# GPRS.net
KiCad netlist of a schematic drawn in Altium Designer
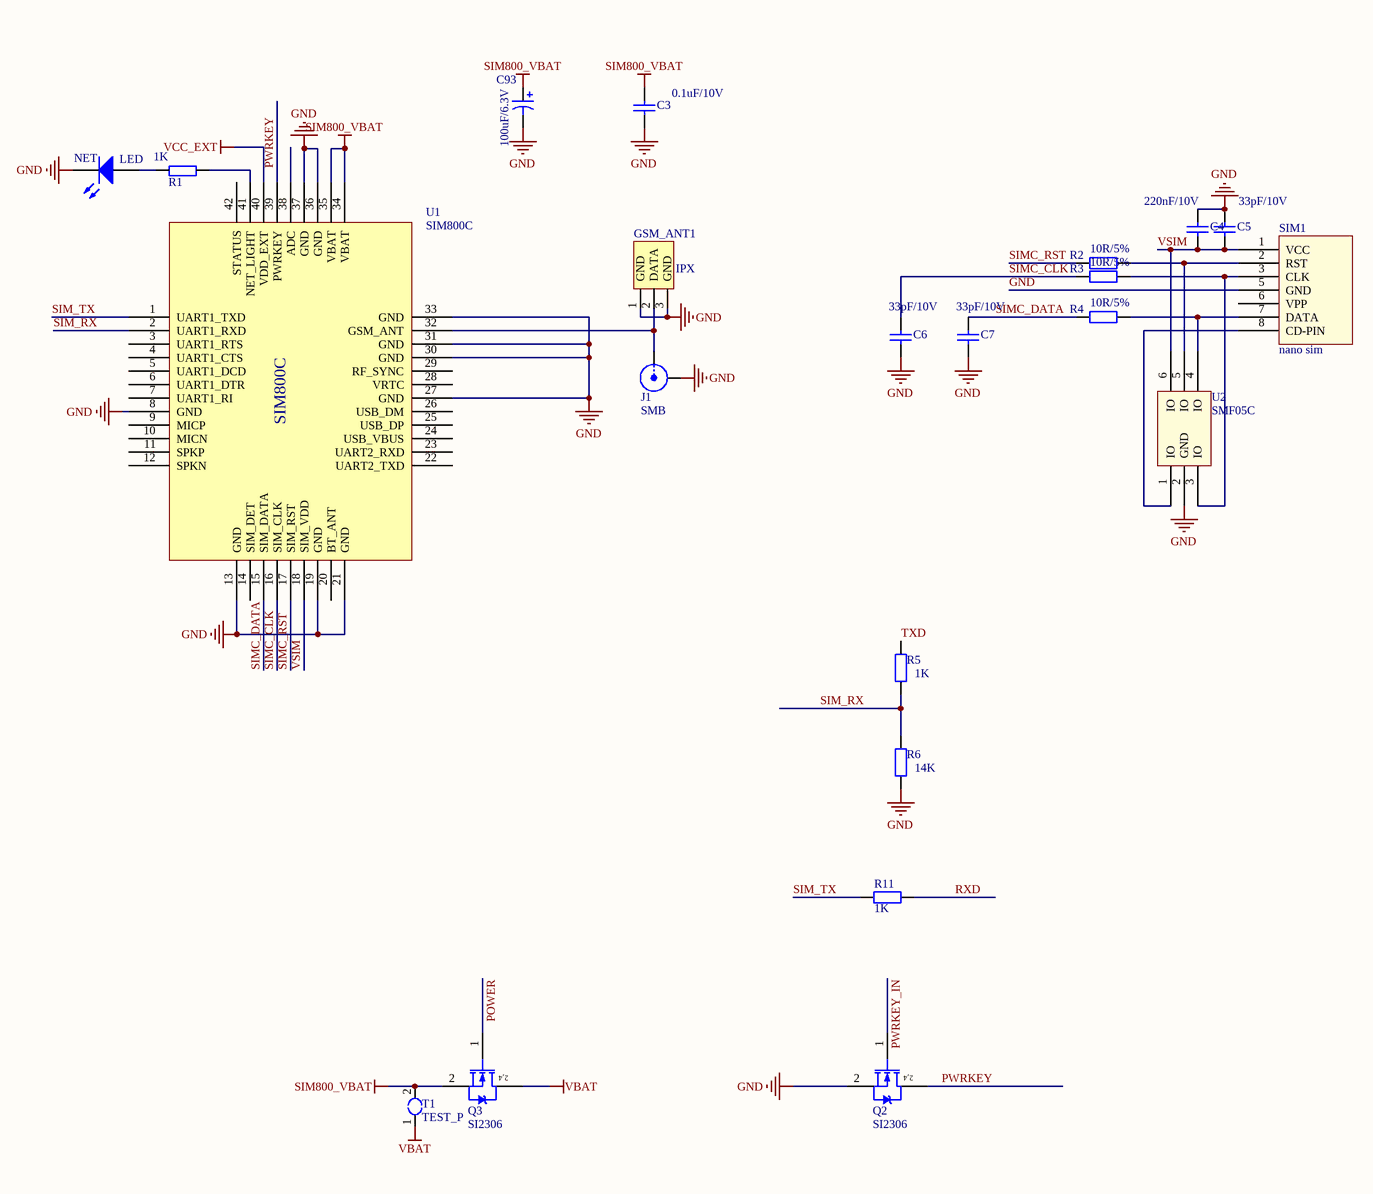
[diagram p0: GPRS.SchDoc]

(export (version "E")
  (design (tool "Eeschema 10.0.6"))
  (components
    (comp (ref "C3")
      (value "0.1uF/10V")
      (footprint "0603C")
      (description "Capacitor")
      (fields (field (name "PUBLISHER") "Altium Limited"))
      (libsource (lib "Miscellaneous Devices") (part "Cap"))
    )
    (comp (ref "C4")
      (value "220nF/10V")
      (footprint "0603C")
      (description "Capacitor")
      (fields (field (name "PUBLISHER") "Altium Limited"))
      (libsource (lib "Miscellaneous Devices") (part "Cap"))
    )
    (comp (ref "C5")
      (value "33pF/10V")
      (footprint "0603C")
      (description "Capacitor")
      (fields (field (name "PUBLISHER") "Altium Limited"))
      (libsource (lib "Miscellaneous Devices") (part "Cap"))
    )
    (comp (ref "C6")
      (value "33pF/10V")
      (footprint "0603C")
      (description "Capacitor")
      (fields (field (name "PUBLISHER") "Altium Limited"))
      (libsource (lib "Miscellaneous Devices") (part "Cap"))
    )
    (comp (ref "C7")
      (value "33pF/10V")
      (footprint "0603C")
      (description "Capacitor")
      (fields (field (name "PUBLISHER") "Altium Limited"))
      (libsource (lib "Miscellaneous Devices") (part "Cap"))
    )
    (comp (ref "C93")
      (value "100uF/6.3V")
      (footprint "7343")
      (description "Polarized Capacitor (Radial)")
      (fields (field (name "PUBLISHER") "Altium Limited"))
      (libsource (lib "Miscellaneous Devices") (part "Cap Pol1"))
    )
    (comp (ref "GSM_ANT1")
      (value "IPX")
      (footprint "IPX")
      (description "IPEX座")
      (libsource (lib "SIM800C 原理图库") (part "IPEX"))
    )
    (comp (ref "J1")
      (value "SMB")
      (footprint "SMA END LAUNCH JACK RECEPTACLE SHORT")
      (description "SMB Straight Connector")
      (fields (field (name "PUBLISHER") "Altium Limited"))
      (libsource (lib "SIM800C 原理图库") (part "SMB"))
    )
    (comp (ref "NET")
      (value "LED")
      (footprint "0603LED")
      (description "Typical RED, GREEN, YELLOW, AMBER GaAs LED")
      (fields (field (name "PUBLISHER") "Altium Limited"))
      (libsource (lib "SIM800C 原理图库") (part "LED2"))
    )
    (comp (ref "Q2")
      (value "SI2306")
      (footprint "SOT23-3")
      (description "BUK92150-55A")
      (fields (field (name "PUBLISHER") "Altium Limited"))
      (libsource (lib "Schlib1") (part "BUK92150-55A"))
    )
    (comp (ref "Q3")
      (value "SI2306")
      (footprint "SOT23-3")
      (description "BUK92150-55A")
      (fields (field (name "PUBLISHER") "Altium Limited"))
      (libsource (lib "Schlib1") (part "BUK92150-55A"))
    )
    (comp (ref "R1") (value "1K") (footprint "0603r") (libsource (lib "SIM800C 原理图库") (part "R")))
    (comp (ref "R2")
      (value "10R/5%")
      (footprint "0603R")
      (description "Resistor")
      (fields (field (name "PUBLISHER") "Altium Limited"))
      (libsource (lib "") (part "Res2_1"))
    )
    (comp (ref "R3")
      (value "10R/5%")
      (footprint "0603R")
      (description "Resistor")
      (fields (field (name "PUBLISHER") "Altium Limited"))
      (libsource (lib "") (part "Res2_1"))
    )
    (comp (ref "R4")
      (value "10R/5%")
      (footprint "0603R")
      (description "Resistor")
      (fields (field (name "PUBLISHER") "Altium Limited"))
      (libsource (lib "") (part "Res2_1"))
    )
    (comp (ref "R5")
      (value "1K")
      (footprint "0603R")
      (description "Resistor")
      (fields (field (name "PUBLISHER") "Altium Limited"))
      (libsource (lib "Miscellaneous Devices") (part "Res2"))
    )
    (comp (ref "R6")
      (value "14K")
      (footprint "0603R")
      (description "Resistor")
      (fields (field (name "PUBLISHER") "Altium Limited"))
      (libsource (lib "Miscellaneous Devices") (part "Res2"))
    )
    (comp (ref "R11")
      (value "1K")
      (footprint "0603R")
      (description "Resistor")
      (fields (field (name "PUBLISHER") "Altium Limited"))
      (libsource (lib "") (part "Res2_2"))
    )
    (comp (ref "SIM1") (value "nano sim") (footprint "Nano SIM") (libsource (lib "lm") (part "nano sim")))
    (comp (ref "T1")
      (value "TEST_P")
      (footprint "TEST_P")
      (libsource (lib "Schlib_20110825") (part "TEST_P"))
    )
    (comp (ref "U1")
      (value "SIM800C")
      (footprint "SIM800C")
      (libsource (lib "SIM800C 原理图库") (part "SIM800C"))
    )
    (comp (ref "U2") (value "SMF05C") (footprint "SC70-6L") (libsource (lib "lm") (part "SMF05C")))
  )
  (nets
    (net (code "1") (name "/POWER") (class "Default")
      (node (ref "Q3") (pin "1") (pinfunction "G_1") (pintype "passive"))
    )
    (net (code "2") (name "/PWRKEY") (class "Default")
      (node (ref "Q2") (pin "3") (pinfunction "D_3") (pintype "passive"))
      (node (ref "U1") (pin "39") (pinfunction "PWRKEY_39") (pintype "passive"))
    )
    (net (code "3") (name "/PWRKEY_IN") (class "Default")
      (node (ref "Q2") (pin "1") (pinfunction "G_1") (pintype "passive"))
    )
    (net (code "4") (name "/RXD") (class "Default")
      (node (ref "R11") (pin "2") (pinfunction "2_2") (pintype "passive"))
    )
    (net (code "5") (name "/SIMC_CLK") (class "Default")
      (node (ref "C6") (pin "1") (pinfunction "1_1") (pintype "passive"))
      (node (ref "R3") (pin "2") (pinfunction "2_2") (pintype "passive"))
      (node (ref "U1") (pin "16") (pinfunction "SIM_CLK_16") (pintype "passive"))
    )
    (net (code "6") (name "/SIMC_DATA") (class "Default")
      (node (ref "C7") (pin "1") (pinfunction "1_1") (pintype "passive"))
      (node (ref "R4") (pin "2") (pinfunction "2_2") (pintype "passive"))
      (node (ref "U1") (pin "15") (pinfunction "SIM_DATA_15") (pintype "passive"))
    )
    (net (code "7") (name "/SIMC_RST") (class "Default")
      (node (ref "R2") (pin "2") (pinfunction "2_2") (pintype "passive"))
      (node (ref "U1") (pin "17") (pinfunction "SIM_RST_17") (pintype "passive"))
    )
    (net (code "8") (name "/SIM_RX") (class "Default")
      (node (ref "R5") (pin "2") (pinfunction "2_2") (pintype "passive"))
      (node (ref "R6") (pin "1") (pinfunction "1_1") (pintype "passive"))
      (node (ref "U1") (pin "2") (pinfunction "UART1_RXD_2") (pintype "passive"))
    )
    (net (code "9") (name "/SIM_TX") (class "Default")
      (node (ref "R11") (pin "1") (pinfunction "1_1") (pintype "passive"))
      (node (ref "U1") (pin "1") (pinfunction "UART1_TXD_1") (pintype "passive"))
    )
    (net (code "10") (name "/TXD") (class "Default")
      (node (ref "R5") (pin "1") (pinfunction "1_1") (pintype "passive"))
    )
    (net (code "11") (name "/VSIM") (class "Default")
      (node (ref "C4") (pin "2") (pinfunction "2_2") (pintype "passive"))
      (node (ref "C5") (pin "2") (pinfunction "2_2") (pintype "passive"))
      (node (ref "SIM1") (pin "1") (pinfunction "VCC_1") (pintype "passive"))
      (node (ref "U1") (pin "18") (pinfunction "SIM_VDD_18") (pintype "passive"))
      (node (ref "U2") (pin "6") (pinfunction "IO_6") (pintype "passive"))
    )
    (net (code "12") (name "GND") (class "Default")
      (node (ref "C3") (pin "2") (pinfunction "2_2") (pintype "passive"))
      (node (ref "C4") (pin "1") (pinfunction "1_1") (pintype "passive"))
      (node (ref "C5") (pin "1") (pinfunction "1_1") (pintype "passive"))
      (node (ref "C6") (pin "2") (pinfunction "2_2") (pintype "passive"))
      (node (ref "C7") (pin "2") (pinfunction "2_2") (pintype "passive"))
      (node (ref "C93") (pin "2") (pinfunction "2_2") (pintype "passive"))
      (node (ref "GSM_ANT1") (pin "1") (pinfunction "GND_1") (pintype "passive"))
      (node (ref "GSM_ANT1") (pin "3") (pinfunction "GND_3") (pintype "passive"))
      (node (ref "J1") (pin "2") (pinfunction "Y_2") (pintype "passive"))
      (node (ref "NET") (pin "2") (pinfunction "K_2") (pintype "passive"))
      (node (ref "Q2") (pin "2") (pinfunction "S_2") (pintype "passive"))
      (node (ref "R6") (pin "2") (pinfunction "2_2") (pintype "passive"))
      (node (ref "SIM1") (pin "5") (pinfunction "GND_5") (pintype "passive"))
      (node (ref "U1") (pin "13") (pinfunction "GND_13") (pintype "passive"))
      (node (ref "U1") (pin "19") (pinfunction "GND_19") (pintype "passive"))
      (node (ref "U1") (pin "21") (pinfunction "GND_21") (pintype "passive"))
      (node (ref "U1") (pin "27") (pinfunction "GND_27") (pintype "passive"))
      (node (ref "U1") (pin "30") (pinfunction "GND_30") (pintype "passive"))
      (node (ref "U1") (pin "31") (pinfunction "GND_31") (pintype "passive"))
      (node (ref "U1") (pin "33") (pinfunction "GND_33") (pintype "passive"))
      (node (ref "U1") (pin "36") (pinfunction "GND_36") (pintype "passive"))
      (node (ref "U1") (pin "37") (pinfunction "GND_37") (pintype "passive"))
      (node (ref "U1") (pin "8") (pinfunction "GND_8") (pintype "passive"))
      (node (ref "U2") (pin "2") (pinfunction "GND_2") (pintype "passive"))
    )
    (net (code "13") (name "Net-(GSM_ANT1-DATA)") (class "Default")
      (node (ref "GSM_ANT1") (pin "2") (pinfunction "DATA_2") (pintype "passive"))
      (node (ref "J1") (pin "1") (pinfunction "X_1") (pintype "passive"))
      (node (ref "U1") (pin "32") (pinfunction "GSM_ANT_32") (pintype "passive"))
    )
    (net (code "14") (name "Net-(NET-A)") (class "Default")
      (node (ref "NET") (pin "1") (pinfunction "A_1") (pintype "passive"))
      (node (ref "R1") (pin "1") (pintype "passive"))
    )
    (net (code "15") (name "Net-(SIM1-CD-PIN)") (class "Default")
      (node (ref "SIM1") (pin "8") (pinfunction "CD-PIN_8") (pintype "passive"))
      (node (ref "U2") (pin "1") (pinfunction "IO_1") (pintype "passive"))
    )
    (net (code "16") (name "Net-(SIM1-CLK)") (class "Default")
      (node (ref "R3") (pin "1") (pinfunction "1_1") (pintype "passive"))
      (node (ref "SIM1") (pin "3") (pinfunction "CLK_3") (pintype "passive"))
      (node (ref "U2") (pin "3") (pinfunction "IO_3") (pintype "passive"))
    )
    (net (code "17") (name "Net-(SIM1-DATA)") (class "Default")
      (node (ref "R4") (pin "1") (pinfunction "1_1") (pintype "passive"))
      (node (ref "SIM1") (pin "7") (pinfunction "DATA_7") (pintype "passive"))
      (node (ref "U2") (pin "4") (pinfunction "IO_4") (pintype "passive"))
    )
    (net (code "18") (name "Net-(SIM1-RST)") (class "Default")
      (node (ref "R2") (pin "1") (pinfunction "1_1") (pintype "passive"))
      (node (ref "SIM1") (pin "2") (pinfunction "RST_2") (pintype "passive"))
      (node (ref "U2") (pin "5") (pinfunction "IO_5") (pintype "passive"))
    )
    (net (code "19") (name "Net-(U1-NET_LIGHT)") (class "Default")
      (node (ref "R1") (pin "2") (pintype "passive"))
      (node (ref "U1") (pin "41") (pinfunction "NET_LIGHT_41") (pintype "passive"))
    )
    (net (code "20") (name "SIM800_VBAT") (class "Default")
      (node (ref "C3") (pin "1") (pinfunction "1_1") (pintype "passive"))
      (node (ref "C93") (pin "1") (pinfunction "1_1") (pintype "passive"))
      (node (ref "Q3") (pin "2") (pinfunction "S_2") (pintype "passive"))
      (node (ref "T1") (pin "2") (pinfunction "2_2") (pintype "passive"))
      (node (ref "U1") (pin "34") (pinfunction "VBAT_34") (pintype "passive"))
      (node (ref "U1") (pin "35") (pinfunction "VBAT_35") (pintype "passive"))
    )
    (net (code "21") (name "VBAT") (class "Default")
      (node (ref "Q3") (pin "3") (pinfunction "D_3") (pintype "passive"))
      (node (ref "T1") (pin "1") (pinfunction "1_1") (pintype "passive"))
    )
    (net (code "22") (name "VCC_EXT") (class "Default")
      (node (ref "U1") (pin "40") (pinfunction "VDD_EXT_40") (pintype "passive"))
    )
    (net (code "23") (name "unconnected-(SIM1-VPP-Pad6)") (class "Default")
      (node (ref "SIM1") (pin "6") (pinfunction "VPP_6") (pintype "passive"))
    )
    (net (code "24") (name "unconnected-(U1-ADC-Pad38)") (class "Default")
      (node (ref "U1") (pin "38") (pinfunction "ADC_38") (pintype "passive"))
    )
    (net (code "25") (name "unconnected-(U1-BT_ANT-Pad20)") (class "Default")
      (node (ref "U1") (pin "20") (pinfunction "BT_ANT_20") (pintype "passive"))
    )
    (net (code "26") (name "unconnected-(U1-MICN-Pad10)") (class "Default")
      (node (ref "U1") (pin "10") (pinfunction "MICN_10") (pintype "passive"))
    )
    (net (code "27") (name "unconnected-(U1-MICP-Pad9)") (class "Default")
      (node (ref "U1") (pin "9") (pinfunction "MICP_9") (pintype "passive"))
    )
    (net (code "28") (name "unconnected-(U1-RF_SYNC-Pad29)") (class "Default")
      (node (ref "U1") (pin "29") (pinfunction "RF_SYNC_29") (pintype "passive"))
    )
    (net (code "29") (name "unconnected-(U1-SIM_DET-Pad14)") (class "Default")
      (node (ref "U1") (pin "14") (pinfunction "SIM_DET_14") (pintype "passive"))
    )
    (net (code "30") (name "unconnected-(U1-SPKN-Pad12)") (class "Default")
      (node (ref "U1") (pin "12") (pinfunction "SPKN_12") (pintype "passive"))
    )
    (net (code "31") (name "unconnected-(U1-SPKP-Pad11)") (class "Default")
      (node (ref "U1") (pin "11") (pinfunction "SPKP_11") (pintype "passive"))
    )
    (net (code "32") (name "unconnected-(U1-STATUS-Pad42)") (class "Default")
      (node (ref "U1") (pin "42") (pinfunction "STATUS_42") (pintype "passive"))
    )
    (net (code "33") (name "unconnected-(U1-UART1_CTS-Pad4)") (class "Default")
      (node (ref "U1") (pin "4") (pinfunction "UART1_CTS_4") (pintype "passive"))
    )
    (net (code "34") (name "unconnected-(U1-UART1_DCD-Pad5)") (class "Default")
      (node (ref "U1") (pin "5") (pinfunction "UART1_DCD_5") (pintype "passive"))
    )
    (net (code "35") (name "unconnected-(U1-UART1_DTR-Pad6)") (class "Default")
      (node (ref "U1") (pin "6") (pinfunction "UART1_DTR_6") (pintype "passive"))
    )
    (net (code "36") (name "unconnected-(U1-UART1_RI-Pad7)") (class "Default")
      (node (ref "U1") (pin "7") (pinfunction "UART1_RI_7") (pintype "passive"))
    )
    (net (code "37") (name "unconnected-(U1-UART1_RTS-Pad3)") (class "Default")
      (node (ref "U1") (pin "3") (pinfunction "UART1_RTS_3") (pintype "passive"))
    )
    (net (code "38") (name "unconnected-(U1-UART2_RXD-Pad23)") (class "Default")
      (node (ref "U1") (pin "23") (pinfunction "UART2_RXD_23") (pintype "passive"))
    )
    (net (code "39") (name "unconnected-(U1-UART2_TXD-Pad22)") (class "Default")
      (node (ref "U1") (pin "22") (pinfunction "UART2_TXD_22") (pintype "passive"))
    )
    (net (code "40") (name "unconnected-(U1-USB_DM-Pad26)") (class "Default")
      (node (ref "U1") (pin "26") (pinfunction "USB_DM_26") (pintype "passive"))
    )
    (net (code "41") (name "unconnected-(U1-USB_DP-Pad25)") (class "Default")
      (node (ref "U1") (pin "25") (pinfunction "USB_DP_25") (pintype "passive"))
    )
    (net (code "42") (name "unconnected-(U1-USB_VBUS-Pad24)") (class "Default")
      (node (ref "U1") (pin "24") (pinfunction "USB_VBUS_24") (pintype "passive"))
    )
    (net (code "43") (name "unconnected-(U1-VRTC-Pad28)") (class "Default")
      (node (ref "U1") (pin "28") (pinfunction "VRTC_28") (pintype "passive"))
    )
  )
)
